# ScrollWheel.net
KiCad netlist of a schematic drawn in Altium Designer
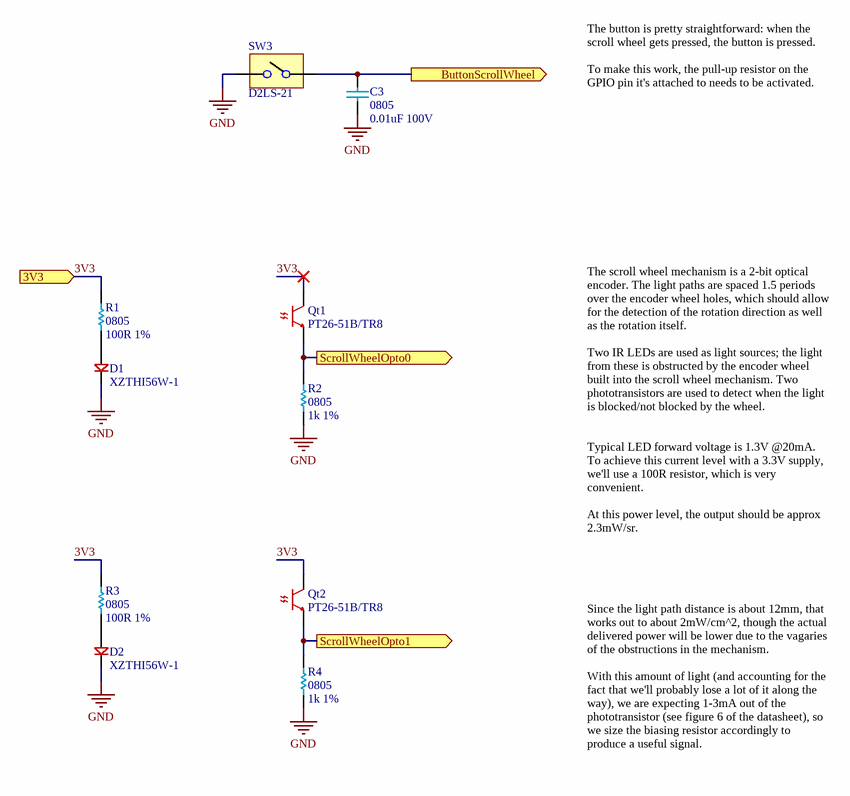
[diagram p0: ScrollWheel.SchDoc]

(export (version "E")
  (design (tool "Eeschema 10.0.6"))
  (components
    (comp (ref "C3")
      (value "0805")
      (footprint "0805")
      (description "0805, X5R or better")
      (fields (field (name "ALTIUM_VALUE") "0.01uF 100V"))
      (libsource (lib "Chip_Passives") (part "Cap 0.01uF 100V"))
    )
    (comp (ref "D1")
      (value "XZTHI56W-1")
      (footprint "XZTHI56W-1")
      (description "Infrared (IR) Emitter 880nm 1.3V 50mA 1mW/sr @ 20mA 30° 2-SMD, No Lead")
      (libsource (lib "LEDs") (part "XZTHI56W-1"))
    )
    (comp (ref "D2")
      (value "XZTHI56W-1")
      (footprint "XZTHI56W-1")
      (description "Infrared (IR) Emitter 880nm 1.3V 50mA 1mW/sr @ 20mA 30° 2-SMD, No Lead")
      (libsource (lib "LEDs") (part "XZTHI56W-1"))
    )
    (comp (ref "Qt1")
      (value "PT26-51B/TR8")
      (footprint "PT26-51B/TR8")
      (description "Phototransistor 940nm Side View 1206 (3216 Metric)")
      (libsource (lib "OptoElectronics") (part "PT26-51B/TR8"))
    )
    (comp (ref "Qt2")
      (value "PT26-51B/TR8")
      (footprint "PT26-51B/TR8")
      (description "Phototransistor 940nm Side View 1206 (3216 Metric)")
      (libsource (lib "OptoElectronics") (part "PT26-51B/TR8"))
    )
    (comp (ref "R1")
      (value "0805")
      (footprint "0805")
      (description "Chip resistor")
      (fields (field (name "ALTIUM_VALUE") "100R 1%"))
      (libsource (lib "Chip_Passives") (part "Res 100R 1% 0805"))
    )
    (comp (ref "R2")
      (value "0805")
      (footprint "0805")
      (description "Chip resistor, 1/8W 100PPM")
      (fields (field (name "ALTIUM_VALUE") "1k 1%"))
      (libsource (lib "Chip_Passives") (part "Res 1k 1% 0805"))
    )
    (comp (ref "R3")
      (value "0805")
      (footprint "0805")
      (description "Chip resistor")
      (fields (field (name "ALTIUM_VALUE") "100R 1%"))
      (libsource (lib "Chip_Passives") (part "Res 100R 1% 0805"))
    )
    (comp (ref "R4")
      (value "0805")
      (footprint "0805")
      (description "Chip resistor, 1/8W 100PPM")
      (fields (field (name "ALTIUM_VALUE") "1k 1%"))
      (libsource (lib "Chip_Passives") (part "Res 1k 1% 0805"))
    )
    (comp (ref "SW3")
      (value "D2LS-21")
      (footprint "D2LS-21")
      (description "Compact Surface-mounting Switch for long durability")
      (libsource (lib "Switches") (part "D2LS-21"))
    )
  )
  (nets
    (net (code "1") (name "/3V3") (class "Default")
      (node (ref "Qt1") (pin "C") (pinfunction "C_C") (pintype "open_collector"))
      (node (ref "Qt2") (pin "C") (pinfunction "C_C") (pintype "open_collector"))
      (node (ref "R1") (pin "2") (pinfunction "2_2") (pintype "passive"))
      (node (ref "R3") (pin "2") (pinfunction "2_2") (pintype "passive"))
    )
    (net (code "2") (name "/ButtonScrollWheel") (class "Default")
      (node (ref "C3") (pin "2") (pinfunction "2_2") (pintype "passive"))
      (node (ref "SW3") (pin "A") (pinfunction "A_A") (pintype "passive"))
    )
    (net (code "3") (name "/ScrollWheelOpto0") (class "Default")
      (node (ref "Qt1") (pin "E") (pinfunction "E_E") (pintype "open_emitter"))
      (node (ref "R2") (pin "2") (pinfunction "2_2") (pintype "passive"))
    )
    (net (code "4") (name "/ScrollWheelOpto1") (class "Default")
      (node (ref "Qt2") (pin "E") (pinfunction "E_E") (pintype "open_emitter"))
      (node (ref "R4") (pin "2") (pinfunction "2_2") (pintype "passive"))
    )
    (net (code "5") (name "GND") (class "Default")
      (node (ref "C3") (pin "1") (pinfunction "1_1") (pintype "passive"))
      (node (ref "D1") (pin "C") (pinfunction "C_C") (pintype "passive"))
      (node (ref "D2") (pin "C") (pinfunction "C_C") (pintype "passive"))
      (node (ref "R2") (pin "1") (pinfunction "1_1") (pintype "passive"))
      (node (ref "R4") (pin "1") (pinfunction "1_1") (pintype "passive"))
      (node (ref "SW3") (pin "B") (pinfunction "B_B") (pintype "passive"))
    )
    (net (code "6") (name "Net-(D1-PadA)") (class "Default")
      (node (ref "D1") (pin "A") (pinfunction "A_A") (pintype "passive"))
      (node (ref "R1") (pin "1") (pinfunction "1_1") (pintype "passive"))
    )
    (net (code "7") (name "Net-(D2-PadA)") (class "Default")
      (node (ref "D2") (pin "A") (pinfunction "A_A") (pintype "passive"))
      (node (ref "R3") (pin "1") (pinfunction "1_1") (pintype "passive"))
    )
  )
)
